# klingel_tueroeffner.net
KiCad netlist of a schematic drawn in EAGLE
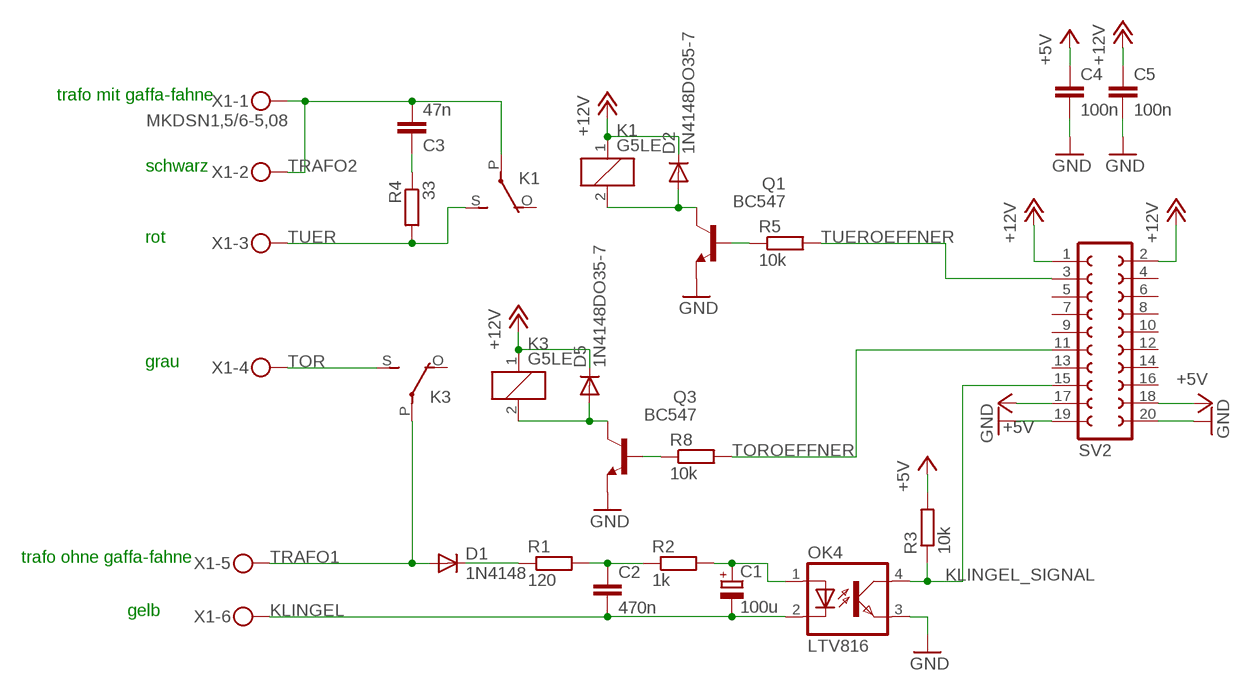
[diagram p0: schematic, sheet 1]

(export (version "E")
  (design (tool "Eeschema 10.0.6"))
  (components
    (comp (ref "C1")
      (value "100u")
      (footprint "eagle-import:E2,5-6")
      (libsource (lib "eagle-import") (part "CPOL-EUE2.5-6"))
    )
    (comp (ref "C2")
      (value "470n")
      (footprint "eagle-import:C050-030X075")
      (libsource (lib "eagle-import") (part "C-EU050-030X075"))
    )
    (comp (ref "C3")
      (value "47n")
      (footprint "eagle-import:C1206")
      (libsource (lib "eagle-import") (part "C-EUC1206"))
    )
    (comp (ref "C4")
      (value "100n")
      (footprint "eagle-import:C0805")
      (libsource (lib "eagle-import") (part "C-EUC0805"))
    )
    (comp (ref "C5")
      (value "100n")
      (footprint "eagle-import:C0805")
      (libsource (lib "eagle-import") (part "C-EUC0805"))
    )
    (comp (ref "D1")
      (value "1N4148")
      (footprint "eagle-import:DO35-7")
      (libsource (lib "eagle-import") (part "1N4148DO35-7"))
    )
    (comp (ref "D2")
      (value "1N4148DO35-7")
      (footprint "eagle-import:DO35-7")
      (libsource (lib "eagle-import") (part "1N4148DO35-7"))
    )
    (comp (ref "D5")
      (value "1N4148DO35-7")
      (footprint "eagle-import:DO35-7")
      (libsource (lib "eagle-import") (part "1N4148DO35-7"))
    )
    (comp (ref "K1")
      (value "G5LE")
      (footprint "eagle-import:G5LE")
      (libsource (lib "eagle-import") (part "G5LE"))
    )
    (comp (ref "K3")
      (value "G5LE")
      (footprint "eagle-import:G5LE")
      (libsource (lib "eagle-import") (part "G5LE"))
    )
    (comp (ref "OK4")
      (value "LTV816")
      (footprint "eagle-import:DIL04")
      (libsource (lib "eagle-import") (part "LTV816"))
    )
    (comp (ref "Q1")
      (value "BC547")
      (footprint "eagle-import:TO92")
      (libsource (lib "eagle-import") (part "BC547"))
    )
    (comp (ref "Q3")
      (value "BC547")
      (footprint "eagle-import:TO92")
      (libsource (lib "eagle-import") (part "BC547"))
    )
    (comp (ref "R1")
      (value "120")
      (footprint "eagle-import:R1206")
      (libsource (lib "eagle-import") (part "R-EU_R1206"))
    )
    (comp (ref "R2")
      (value "1k")
      (footprint "eagle-import:R1206")
      (libsource (lib "eagle-import") (part "R-EU_R1206"))
    )
    (comp (ref "R3")
      (value "10k")
      (footprint "eagle-import:R0805")
      (libsource (lib "eagle-import") (part "R-EU_R0805"))
    )
    (comp (ref "R4")
      (value "33")
      (footprint "eagle-import:R1206")
      (libsource (lib "eagle-import") (part "R-EU_R1206"))
    )
    (comp (ref "R5")
      (value "10k")
      (footprint "eagle-import:0204_7")
      (libsource (lib "eagle-import") (part "R-EU_0204/7"))
    )
    (comp (ref "R8")
      (value "10k")
      (footprint "eagle-import:R0805")
      (libsource (lib "eagle-import") (part "R-EU_R0805"))
    )
    (comp (ref "SV2")
      (value "FE10-2")
      (footprint "eagle-import:FE10-2")
      (libsource (lib "eagle-import") (part "FE10-2"))
    )
    (comp (ref "X1")
      (value "MKDSN1,5/6-5,08")
      (footprint "eagle-import:MKDSN1,5_6-5,08")
      (fields (field (name "MPN") "SMKDSN1,5/6-5,08"))
      (libsource (lib "eagle-import") (part "MKDSN1,5/6-5,08"))
    )
  )
  (nets
    (net (code "1") (name "+5V") (class "Default")
      (node (ref "C4") (pin "1") (pinfunction "1_1") (pintype "passive"))
      (node (ref "R3") (pin "2") (pinfunction "2_2") (pintype "passive"))
      (node (ref "SV2") (pin "17") (pinfunction "17_17") (pintype "passive"))
      (node (ref "SV2") (pin "18") (pinfunction "18_18") (pintype "passive"))
    )
    (net (code "2") (name "+12V") (class "Default")
      (node (ref "C5") (pin "1") (pinfunction "1_1") (pintype "passive"))
      (node (ref "D2") (pin "C") (pinfunction "C_C") (pintype "passive"))
      (node (ref "D5") (pin "C") (pinfunction "C_C") (pintype "passive"))
      (node (ref "K1") (pin "1") (pinfunction "1_1") (pintype "passive"))
      (node (ref "K3") (pin "1") (pinfunction "1_1") (pintype "passive"))
      (node (ref "SV2") (pin "1") (pinfunction "1_1") (pintype "passive"))
      (node (ref "SV2") (pin "2") (pinfunction "2_2") (pintype "passive"))
    )
    (net (code "3") (name "/KLINGEL") (class "Default")
      (node (ref "C1") (pin "-") (pinfunction "-_-") (pintype "passive"))
      (node (ref "C2") (pin "2") (pinfunction "2_2") (pintype "passive"))
      (node (ref "OK4") (pin "2") (pinfunction "C_2") (pintype "passive"))
      (node (ref "X1") (pin "6") (pinfunction "KL_6") (pintype "passive"))
    )
    (net (code "4") (name "/KLINGEL_SIGNAL") (class "Default")
      (node (ref "OK4") (pin "4") (pinfunction "COL_4") (pintype "passive"))
      (node (ref "R3") (pin "1") (pinfunction "1_1") (pintype "passive"))
      (node (ref "SV2") (pin "15") (pinfunction "15_15") (pintype "passive"))
    )
    (net (code "5") (name "/TOR") (class "Default")
      (node (ref "K3") (pin "S") (pinfunction "S_S") (pintype "passive"))
      (node (ref "X1") (pin "4") (pinfunction "KL_4") (pintype "passive"))
    )
    (net (code "6") (name "/TOROEFFNER") (class "Default")
      (node (ref "R8") (pin "2") (pinfunction "2_2") (pintype "passive"))
      (node (ref "SV2") (pin "11") (pinfunction "11_11") (pintype "passive"))
    )
    (net (code "7") (name "/TRAFO1") (class "Default")
      (node (ref "D1") (pin "A") (pinfunction "A_A") (pintype "passive"))
      (node (ref "K3") (pin "P") (pinfunction "P_P") (pintype "passive"))
      (node (ref "X1") (pin "5") (pinfunction "KL_5") (pintype "passive"))
    )
    (net (code "8") (name "/TRAFO2") (class "Default")
      (node (ref "C3") (pin "2") (pinfunction "2_2") (pintype "passive"))
      (node (ref "K1") (pin "P") (pinfunction "P_P") (pintype "passive"))
      (node (ref "X1") (pin "1") (pinfunction "KL_1") (pintype "passive"))
      (node (ref "X1") (pin "2") (pinfunction "KL_2") (pintype "passive"))
    )
    (net (code "9") (name "/TUER") (class "Default")
      (node (ref "K1") (pin "S") (pinfunction "S_S") (pintype "passive"))
      (node (ref "R4") (pin "2") (pinfunction "2_2") (pintype "passive"))
      (node (ref "X1") (pin "3") (pinfunction "KL_3") (pintype "passive"))
    )
    (net (code "10") (name "/TUEROEFFNER") (class "Default")
      (node (ref "R5") (pin "2") (pinfunction "2_2") (pintype "passive"))
      (node (ref "SV2") (pin "3") (pinfunction "3_3") (pintype "passive"))
    )
    (net (code "11") (name "GND") (class "Default")
      (node (ref "C4") (pin "2") (pinfunction "2_2") (pintype "passive"))
      (node (ref "C5") (pin "2") (pinfunction "2_2") (pintype "passive"))
      (node (ref "OK4") (pin "3") (pinfunction "EMIT_3") (pintype "passive"))
      (node (ref "Q1") (pin "1") (pinfunction "E_1") (pintype "passive"))
      (node (ref "Q3") (pin "1") (pinfunction "E_1") (pintype "passive"))
      (node (ref "SV2") (pin "19") (pinfunction "19_19") (pintype "passive"))
      (node (ref "SV2") (pin "20") (pinfunction "20_20") (pintype "passive"))
    )
    (net (code "12") (name "Net-(C2-Pad1)") (class "Default")
      (node (ref "C2") (pin "1") (pinfunction "1_1") (pintype "passive"))
      (node (ref "R1") (pin "2") (pinfunction "2_2") (pintype "passive"))
      (node (ref "R2") (pin "1") (pinfunction "1_1") (pintype "passive"))
    )
    (net (code "13") (name "Net-(C3-Pad1)") (class "Default")
      (node (ref "C3") (pin "1") (pinfunction "1_1") (pintype "passive"))
      (node (ref "R4") (pin "1") (pinfunction "1_1") (pintype "passive"))
    )
    (net (code "14") (name "Net-(D1-PadC)") (class "Default")
      (node (ref "D1") (pin "C") (pinfunction "C_C") (pintype "passive"))
      (node (ref "R1") (pin "1") (pinfunction "1_1") (pintype "passive"))
    )
    (net (code "15") (name "Net-(OK4-A)") (class "Default")
      (node (ref "C1") (pin "+") (pinfunction "+_+") (pintype "passive"))
      (node (ref "OK4") (pin "1") (pinfunction "A_1") (pintype "passive"))
      (node (ref "R2") (pin "2") (pinfunction "2_2") (pintype "passive"))
    )
    (net (code "16") (name "Net-(Q1-B)") (class "Default")
      (node (ref "Q1") (pin "2") (pinfunction "B_2") (pintype "passive"))
      (node (ref "R5") (pin "1") (pinfunction "1_1") (pintype "passive"))
    )
    (net (code "17") (name "Net-(Q1-C)") (class "Default")
      (node (ref "D2") (pin "A") (pinfunction "A_A") (pintype "passive"))
      (node (ref "K1") (pin "2") (pinfunction "2_2") (pintype "passive"))
      (node (ref "Q1") (pin "3") (pinfunction "C_3") (pintype "passive"))
    )
    (net (code "18") (name "Net-(Q3-B)") (class "Default")
      (node (ref "Q3") (pin "2") (pinfunction "B_2") (pintype "passive"))
      (node (ref "R8") (pin "1") (pinfunction "1_1") (pintype "passive"))
    )
    (net (code "19") (name "Net-(Q3-C)") (class "Default")
      (node (ref "D5") (pin "A") (pinfunction "A_A") (pintype "passive"))
      (node (ref "K3") (pin "2") (pinfunction "2_2") (pintype "passive"))
      (node (ref "Q3") (pin "3") (pinfunction "C_3") (pintype "passive"))
    )
    (net (code "20") (name "unconnected-(K1-PadO)") (class "Default")
      (node (ref "K1") (pin "O") (pinfunction "O_O") (pintype "passive"))
    )
    (net (code "21") (name "unconnected-(K3-PadO)") (class "Default")
      (node (ref "K3") (pin "O") (pinfunction "O_O") (pintype "passive"))
    )
    (net (code "22") (name "unconnected-(SV2-Pad4)") (class "Default")
      (node (ref "SV2") (pin "4") (pinfunction "4_4") (pintype "passive"))
    )
    (net (code "23") (name "unconnected-(SV2-Pad5)") (class "Default")
      (node (ref "SV2") (pin "5") (pinfunction "5_5") (pintype "passive"))
    )
    (net (code "24") (name "unconnected-(SV2-Pad6)") (class "Default")
      (node (ref "SV2") (pin "6") (pinfunction "6_6") (pintype "passive"))
    )
    (net (code "25") (name "unconnected-(SV2-Pad7)") (class "Default")
      (node (ref "SV2") (pin "7") (pinfunction "7_7") (pintype "passive"))
    )
    (net (code "26") (name "unconnected-(SV2-Pad8)") (class "Default")
      (node (ref "SV2") (pin "8") (pinfunction "8_8") (pintype "passive"))
    )
    (net (code "27") (name "unconnected-(SV2-Pad9)") (class "Default")
      (node (ref "SV2") (pin "9") (pinfunction "9_9") (pintype "passive"))
    )
    (net (code "28") (name "unconnected-(SV2-Pad10)") (class "Default")
      (node (ref "SV2") (pin "10") (pinfunction "10_10") (pintype "passive"))
    )
    (net (code "29") (name "unconnected-(SV2-Pad12)") (class "Default")
      (node (ref "SV2") (pin "12") (pinfunction "12_12") (pintype "passive"))
    )
    (net (code "30") (name "unconnected-(SV2-Pad13)") (class "Default")
      (node (ref "SV2") (pin "13") (pinfunction "13_13") (pintype "passive"))
    )
    (net (code "31") (name "unconnected-(SV2-Pad14)") (class "Default")
      (node (ref "SV2") (pin "14") (pinfunction "14_14") (pintype "passive"))
    )
    (net (code "32") (name "unconnected-(SV2-Pad16)") (class "Default")
      (node (ref "SV2") (pin "16") (pinfunction "16_16") (pintype "passive"))
    )
  )
)
